# FC_Main.net
KiCad netlist of a schematic drawn in Altium Designer
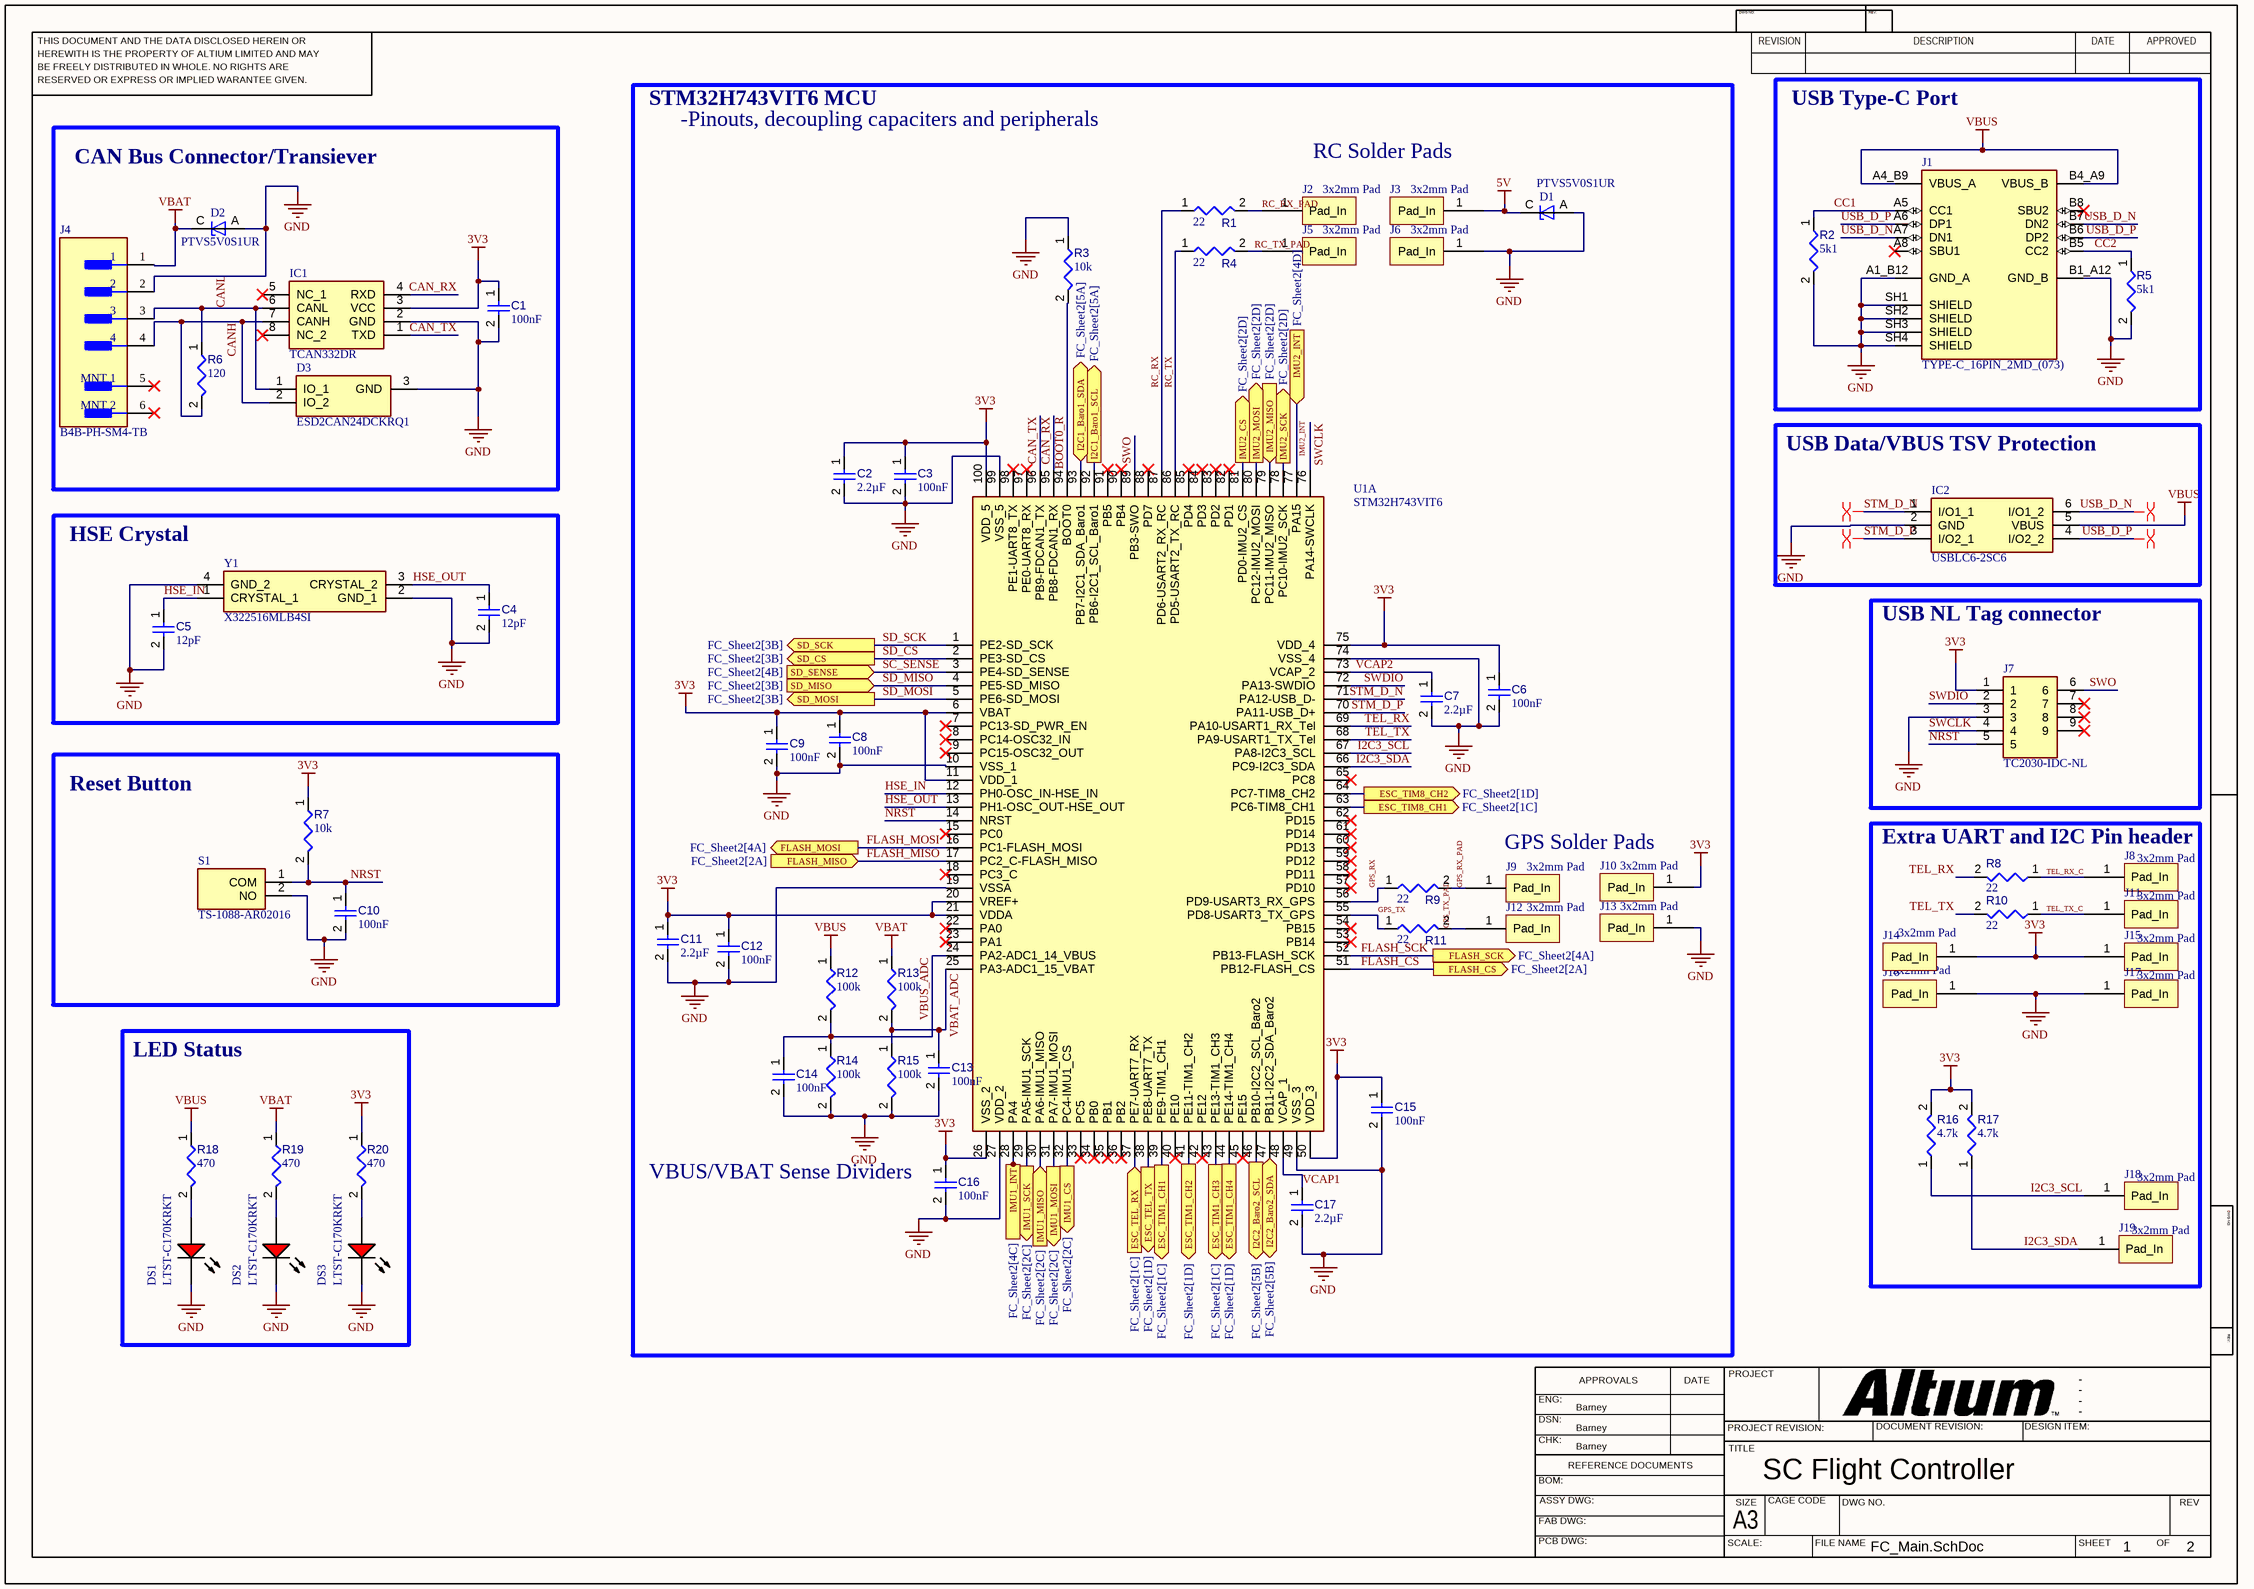
[diagram p0: FC_Main.SchDoc]

(export (version "E")
  (design (tool "Eeschema 10.0.6"))
  (components
    (comp (ref "C1")
      (value "100nF")
      (footprint "CAPC0402(1005)60_L")
      (description "Chip Capacitor, 100nF +/-20%, 10V, 0402, Thickness 0.6 mm")
      (fields (field (name "TOLERANCE") "20%") (field (name "Comment") "Capacitor 100nF +/-20% 10V 0402"))
      (libsource (lib "Barney's Workspace") (part "CAP-NP-2"))
    )
    (comp (ref "C2")
      (value "2.2µF")
      (footprint "CAPC0402(1005)60_L")
      (description "Chip Capacitor, 2,2µF +/-20%, 10V, 0402, Thickness 0.6 mm")
      (fields (field (name "TOLERANCE") "10%") (field (name "Comment") "Capacitor 2,2µF +/-20% 10V 0402"))
      (libsource (lib "Barney's Workspace") (part "CAP-NP-2"))
    )
    (comp (ref "C3")
      (value "100nF")
      (footprint "CAPC0402(1005)60_L")
      (description "Chip Capacitor, 100nF +/-20%, 10V, 0402, Thickness 0.6 mm")
      (fields (field (name "TOLERANCE") "20%") (field (name "Comment") "Capacitor 100nF +/-20% 10V 0402"))
      (libsource (lib "Barney's Workspace") (part "CAP-NP-2"))
    )
    (comp (ref "C4")
      (value "12pF")
      (footprint "CAPC0402(1005)33_L")
      (description "Chip Capacitor, 12pF +/-10%, 50V, 0402, Thickness 0.33 mm")
      (fields (field (name "TOLERANCE") "20%") (field (name "Comment") "Capacitor 12pF +/-10% 50V 0402"))
      (libsource (lib "Barney's Workspace") (part "CAP-NP-2"))
    )
    (comp (ref "C5")
      (value "12pF")
      (footprint "CAPC0402(1005)33_L")
      (description "Chip Capacitor, 12pF +/-10%, 50V, 0402, Thickness 0.33 mm")
      (fields (field (name "TOLERANCE") "20%") (field (name "Comment") "Capacitor 12pF +/-10% 50V 0402"))
      (libsource (lib "Barney's Workspace") (part "CAP-NP-2"))
    )
    (comp (ref "C6")
      (value "100nF")
      (footprint "CAPC0402(1005)60_L")
      (description "Chip Capacitor, 100nF +/-20%, 10V, 0402, Thickness 0.6 mm")
      (fields (field (name "TOLERANCE") "20%") (field (name "Comment") "Capacitor 100nF +/-20% 10V 0402"))
      (libsource (lib "Barney's Workspace") (part "CAP-NP-2"))
    )
    (comp (ref "C7")
      (value "2.2µF")
      (footprint "CAPC0402(1005)60_L")
      (description "Chip Capacitor, 2,2µF +/-20%, 10V, 0402, Thickness 0.6 mm")
      (fields (field (name "TOLERANCE") "10%") (field (name "Comment") "Capacitor 2,2µF +/-20% 10V 0402"))
      (libsource (lib "Barney's Workspace") (part "CAP-NP-2"))
    )
    (comp (ref "C8")
      (value "100nF")
      (footprint "CAPC0402(1005)60_L")
      (description "Chip Capacitor, 100nF +/-20%, 10V, 0402, Thickness 0.6 mm")
      (fields (field (name "TOLERANCE") "20%") (field (name "Comment") "Capacitor 100nF +/-20% 10V 0402"))
      (libsource (lib "Barney's Workspace") (part "CAP-NP-2"))
    )
    (comp (ref "C9")
      (value "100nF")
      (footprint "CAPC0402(1005)60_L")
      (description "Chip Capacitor, 100nF +/-20%, 10V, 0402, Thickness 0.6 mm")
      (fields (field (name "TOLERANCE") "20%") (field (name "Comment") "Capacitor 100nF +/-20% 10V 0402"))
      (libsource (lib "Barney's Workspace") (part "CAP-NP-2"))
    )
    (comp (ref "C10")
      (value "100nF")
      (footprint "CAPC0402(1005)60_L")
      (description "Chip Capacitor, 100nF +/-20%, 10V, 0402, Thickness 0.6 mm")
      (fields (field (name "TOLERANCE") "20%") (field (name "Comment") "Capacitor 100nF +/-20% 10V 0402"))
      (libsource (lib "Barney's Workspace") (part "CAP-NP-2"))
    )
    (comp (ref "C11")
      (value "2.2µF")
      (footprint "CAPC0402(1005)60_L")
      (description "Chip Capacitor, 2,2µF +/-20%, 10V, 0402, Thickness 0.6 mm")
      (fields (field (name "TOLERANCE") "10%") (field (name "Comment") "Capacitor 2,2µF +/-20% 10V 0402"))
      (libsource (lib "Barney's Workspace") (part "CAP-NP-2"))
    )
    (comp (ref "C12")
      (value "100nF")
      (footprint "CAPC0402(1005)60_L")
      (description "Chip Capacitor, 100nF +/-20%, 10V, 0402, Thickness 0.6 mm")
      (fields (field (name "TOLERANCE") "20%") (field (name "Comment") "Capacitor 100nF +/-20% 10V 0402"))
      (libsource (lib "Barney's Workspace") (part "CAP-NP-2"))
    )
    (comp (ref "C13")
      (value "100nF")
      (footprint "CAPC0402(1005)60_L")
      (description "Chip Capacitor, 100nF +/-20%, 10V, 0402, Thickness 0.6 mm")
      (fields (field (name "TOLERANCE") "20%") (field (name "Comment") "Capacitor 100nF +/-20% 10V 0402"))
      (libsource (lib "Barney's Workspace") (part "CAP-NP-2"))
    )
    (comp (ref "C14")
      (value "100nF")
      (footprint "CAPC0402(1005)60_L")
      (description "Chip Capacitor, 100nF +/-20%, 10V, 0402, Thickness 0.6 mm")
      (fields (field (name "TOLERANCE") "20%") (field (name "Comment") "Capacitor 100nF +/-20% 10V 0402"))
      (libsource (lib "Barney's Workspace") (part "CAP-NP-2"))
    )
    (comp (ref "C15")
      (value "100nF")
      (footprint "CAPC0402(1005)60_L")
      (description "Chip Capacitor, 100nF +/-20%, 10V, 0402, Thickness 0.6 mm")
      (fields (field (name "TOLERANCE") "20%") (field (name "Comment") "Capacitor 100nF +/-20% 10V 0402"))
      (libsource (lib "Barney's Workspace") (part "CAP-NP-2"))
    )
    (comp (ref "C16")
      (value "100nF")
      (footprint "CAPC0402(1005)60_L")
      (description "Chip Capacitor, 100nF +/-20%, 10V, 0402, Thickness 0.6 mm")
      (fields (field (name "TOLERANCE") "20%") (field (name "Comment") "Capacitor 100nF +/-20% 10V 0402"))
      (libsource (lib "Barney's Workspace") (part "CAP-NP-2"))
    )
    (comp (ref "C17")
      (value "2.2µF")
      (footprint "CAPC0402(1005)60_L")
      (description "Chip Capacitor, 2,2µF +/-20%, 10V, 0402, Thickness 0.6 mm")
      (fields (field (name "TOLERANCE") "10%") (field (name "Comment") "Capacitor 2,2µF +/-20% 10V 0402"))
      (libsource (lib "Barney's Workspace") (part "CAP-NP-2"))
    )
    (comp (ref "D1")
      (value "PTVS5V0S1UR")
      (footprint "TVS_PTVS5V0S1UR")
      (description "9.2V Clamp 43.5A Ipp Tvs Diode Surface Mount SOD-123W")
      (fields (field (name "MF") "Nexperia USA"))
      (libsource (lib "Barney's Workspace") (part "PTVS5V0S1UR"))
    )
    (comp (ref "D2")
      (value "PTVS5V0S1UR")
      (footprint "TVS_PTVS5V0S1UR")
      (description "9.2V Clamp 43.5A Ipp Tvs Diode Surface Mount SOD-123W")
      (fields (field (name "MF") "Nexperia USA"))
      (libsource (lib "Barney's Workspace") (part "PTVS5V0S1UR"))
    )
    (comp (ref "D3")
      (value "ESD2CAN24DCKRQ1")
      (footprint "SamacSys:SOT65P210X110-3N")
      (description "TVS Diode (Bi-directional)")
      (fields (field (name "MOUSER PART NUMBER") "595-ESD2CAN24DCKRQ1"))
      (libsource (lib "*") (part "ESD2CAN24DCKRQ1"))
    )
    (comp (ref "DS1")
      (value "LTST-C170KRKT")
      (footprint "LTST-C170KRKT_V")
      (description "LED Red, 75 mW, 54 mcd, -55 to 85 degC, 2-Pin SMD, RoHS, Tape and Reel")
      (fields (field (name "MANUFACTURER") "Lite-On"))
      (libsource (lib "Altium Content Vault") (part "LED-RED-AK-2"))
    )
    (comp (ref "DS2")
      (value "LTST-C170KRKT")
      (footprint "LTST-C170KRKT_V")
      (description "LED Red, 75 mW, 54 mcd, -55 to 85 degC, 2-Pin SMD, RoHS, Tape and Reel")
      (fields (field (name "MANUFACTURER") "Lite-On"))
      (libsource (lib "Altium Content Vault") (part "LED-RED-AK-2"))
    )
    (comp (ref "DS3")
      (value "LTST-C170KRKT")
      (footprint "LTST-C170KRKT_V")
      (description "LED Red, 75 mW, 54 mcd, -55 to 85 degC, 2-Pin SMD, RoHS, Tape and Reel")
      (fields (field (name "MANUFACTURER") "Lite-On"))
      (libsource (lib "Altium Content Vault") (part "LED-RED-AK-2"))
    )
    (comp (ref "IC1")
      (value "TCAN332DR")
      (footprint "SamacSys:SOIC127P600X175-8N")
      (description "Integrated Circuit")
      (fields (field (name "MOUSER PART NUMBER") "595-TCAN332DR"))
      (libsource (lib "*") (part "TCAN332DR"))
    )
    (comp (ref "IC2")
      (value "USBLC6-2SC6")
      (footprint "SamacSys:SOT95P280X145-6N")
      (description "Integrated Circuit")
      (fields (field (name "MOUSER PART NUMBER") "511-USBLC6-2SC6"))
      (libsource (lib "*") (part "USBLC6-2SC6"))
    )
    (comp (ref "J1")
      (value "TYPE-C_16PIN_2MD_(073)")
      (footprint "SHOUHAN_TYPE-C_16PIN_2MD_(073)")
      (description "DC-5V 5A Type C USB")
      (fields (field (name "MP") "TYPE-C 16PIN 2MD (073)") (field (name "MF") "Shouhan"))
      (libsource (lib "Barney's Workspace") (part "TYPE-C_16PIN_2MD_(073)"))
    )
    (comp (ref "J2")
      (value "3x2mm Pad")
      (footprint "3x2mm Pad-Footprint-1")
      (description "3mm x 2mm Pad to solder")
      (libsource (lib "Barney's Workspace") (part "3x2mm Pad-Symbol-1"))
    )
    (comp (ref "J3")
      (value "3x2mm Pad")
      (footprint "3x2mm Pad-Footprint-1")
      (description "3mm x 2mm Pad to solder")
      (libsource (lib "") (part "3x2mm Pad-Symbol-1_1"))
    )
    (comp (ref "J4")
      (value "B4B-PH-SM4-TB")
      (footprint "FP-B4B-PH-SM4-TB-MFG")
      (description "CONN HEADER SMD 4POS 2MM")
      (libsource (lib "Altium Content Vault") (part "f4320a1371cd6270e33bce1916c33c0"))
    )
    (comp (ref "J5")
      (value "3x2mm Pad")
      (footprint "3x2mm Pad-Footprint-1")
      (description "3mm x 2mm Pad to solder")
      (libsource (lib "Barney's Workspace") (part "3x2mm Pad-Symbol-1"))
    )
    (comp (ref "J6")
      (value "3x2mm Pad")
      (footprint "3x2mm Pad-Footprint-1")
      (description "3mm x 2mm Pad to solder")
      (libsource (lib "") (part "3x2mm Pad-Symbol-1_1"))
    )
    (comp (ref "J7")
      (value "TC2030-IDC-NL")
      (footprint "SamacSys:TC2030IDCNL")
      (description "Connector")
      (libsource (lib "*") (part "TC2030-IDC-NL"))
    )
    (comp (ref "J8")
      (value "3x2mm Pad")
      (footprint "3x2mm Pad-Footprint-1")
      (description "3mm x 2mm Pad to solder")
      (libsource (lib "Barney's Workspace") (part "3x2mm Pad-Symbol-1"))
    )
    (comp (ref "J9")
      (value "3x2mm Pad")
      (footprint "3x2mm Pad-Footprint-1")
      (description "3mm x 2mm Pad to solder")
      (libsource (lib "Barney's Workspace") (part "3x2mm Pad-Symbol-1"))
    )
    (comp (ref "J10")
      (value "3x2mm Pad")
      (footprint "3x2mm Pad-Footprint-1")
      (description "3mm x 2mm Pad to solder")
      (libsource (lib "") (part "3x2mm Pad-Symbol-1_1"))
    )
    (comp (ref "J11")
      (value "3x2mm Pad")
      (footprint "3x2mm Pad-Footprint-1")
      (description "3mm x 2mm Pad to solder")
      (libsource (lib "Barney's Workspace") (part "3x2mm Pad-Symbol-1"))
    )
    (comp (ref "J12")
      (value "3x2mm Pad")
      (footprint "3x2mm Pad-Footprint-1")
      (description "3mm x 2mm Pad to solder")
      (libsource (lib "Barney's Workspace") (part "3x2mm Pad-Symbol-1"))
    )
    (comp (ref "J13")
      (value "3x2mm Pad")
      (footprint "3x2mm Pad-Footprint-1")
      (description "3mm x 2mm Pad to solder")
      (libsource (lib "") (part "3x2mm Pad-Symbol-1_1"))
    )
    (comp (ref "J14")
      (value "3x2mm Pad")
      (footprint "3x2mm Pad-Footprint-1")
      (description "3mm x 2mm Pad to solder")
      (libsource (lib "") (part "3x2mm Pad-Symbol-1_1"))
    )
    (comp (ref "J15")
      (value "3x2mm Pad")
      (footprint "3x2mm Pad-Footprint-1")
      (description "3mm x 2mm Pad to solder")
      (libsource (lib "Barney's Workspace") (part "3x2mm Pad-Symbol-1"))
    )
    (comp (ref "J16")
      (value "3x2mm Pad")
      (footprint "3x2mm Pad-Footprint-1")
      (description "3mm x 2mm Pad to solder")
      (libsource (lib "") (part "3x2mm Pad-Symbol-1_1"))
    )
    (comp (ref "J17")
      (value "3x2mm Pad")
      (footprint "3x2mm Pad-Footprint-1")
      (description "3mm x 2mm Pad to solder")
      (libsource (lib "Barney's Workspace") (part "3x2mm Pad-Symbol-1"))
    )
    (comp (ref "J18")
      (value "3x2mm Pad")
      (footprint "3x2mm Pad-Footprint-1")
      (description "3mm x 2mm Pad to solder")
      (libsource (lib "Barney's Workspace") (part "3x2mm Pad-Symbol-1"))
    )
    (comp (ref "J19")
      (value "3x2mm Pad")
      (footprint "3x2mm Pad-Footprint-1")
      (description "3mm x 2mm Pad to solder")
      (libsource (lib "Barney's Workspace") (part "3x2mm Pad-Symbol-1"))
    )
    (comp (ref "R1")
      (value "22")
      (footprint "RESC0402(1005)_L")
      (description "Chip Resistor, 22Ohms, +/-1 %, 63 mW, -55 to 155 degC, 0402")
      (fields (field (name "TOLERANCE") "1%") (field (name "POWER") "63mW"))
      (libsource (lib "Barney's Workspace") (part "RES-2"))
    )
    (comp (ref "R2")
      (value "5k1")
      (footprint "RESC0402(1005)_L")
      (description "Chip Resistor, 5.1 kOhms, +/-1 %, 63 mW, -55 to 155 degC, 0402")
      (fields (field (name "TOLERANCE") "1%") (field (name "POWER") "63mW"))
      (libsource (lib "Barney's Workspace") (part "RES-2"))
    )
    (comp (ref "R3")
      (value "10k")
      (footprint "RESC0402(1005)_L")
      (description "Chip Resistor, 10 kOhms, +/-1 %, 63 mW, -55 to 125 degC, 0402")
      (fields (field (name "POWER") "63mW") (field (name "TOLERANCE") "1%"))
      (libsource (lib "Barney's Workspace") (part "RES-2"))
    )
    (comp (ref "R4")
      (value "22")
      (footprint "RESC0402(1005)_L")
      (description "Chip Resistor, 22Ohms, +/-1 %, 63 mW, -55 to 155 degC, 0402")
      (fields (field (name "TOLERANCE") "1%") (field (name "POWER") "63mW"))
      (libsource (lib "Barney's Workspace") (part "RES-2"))
    )
    (comp (ref "R5")
      (value "5k1")
      (footprint "RESC0402(1005)_L")
      (description "Chip Resistor, 5.1 kOhms, +/-1 %, 63 mW, -55 to 155 degC, 0402")
      (fields (field (name "TOLERANCE") "1%") (field (name "POWER") "63mW"))
      (libsource (lib "Barney's Workspace") (part "RES-2"))
    )
    (comp (ref "R6")
      (value "120")
      (footprint "RESC0402(1005)_L")
      (description "Chip Resistor, 120 Ohms, +/-1 %, 63 mW, -55 to 155 degC, 0402")
      (fields (field (name "TOLERANCE") "1%") (field (name "POWER") "63mW"))
      (libsource (lib "Barney's Workspace") (part "RES-2"))
    )
    (comp (ref "R7")
      (value "10k")
      (footprint "RESC0402(1005)_L")
      (description "Chip Resistor, 10 kOhms, +/-1 %, 63 mW, -55 to 125 degC, 0402")
      (fields (field (name "POWER") "63mW") (field (name "TOLERANCE") "1%"))
      (libsource (lib "Barney's Workspace") (part "RES-2"))
    )
    (comp (ref "R8")
      (value "22")
      (footprint "RESC0402(1005)_L")
      (description "Chip Resistor, 22Ohms, +/-1 %, 63 mW, -55 to 155 degC, 0402")
      (fields (field (name "TOLERANCE") "1%") (field (name "POWER") "63mW"))
      (libsource (lib "Barney's Workspace") (part "RES-2"))
    )
    (comp (ref "R9")
      (value "22")
      (footprint "RESC0402(1005)_L")
      (description "Chip Resistor, 22Ohms, +/-1 %, 63 mW, -55 to 155 degC, 0402")
      (fields (field (name "TOLERANCE") "1%") (field (name "POWER") "63mW"))
      (libsource (lib "Barney's Workspace") (part "RES-2"))
    )
    (comp (ref "R10")
      (value "22")
      (footprint "RESC0402(1005)_L")
      (description "Chip Resistor, 22Ohms, +/-1 %, 63 mW, -55 to 155 degC, 0402")
      (fields (field (name "TOLERANCE") "1%") (field (name "POWER") "63mW"))
      (libsource (lib "Barney's Workspace") (part "RES-2"))
    )
    (comp (ref "R11")
      (value "22")
      (footprint "RESC0402(1005)_L")
      (description "Chip Resistor, 22Ohms, +/-1 %, 63 mW, -55 to 155 degC, 0402")
      (fields (field (name "TOLERANCE") "1%") (field (name "POWER") "63mW"))
      (libsource (lib "Barney's Workspace") (part "RES-2"))
    )
    (comp (ref "R12")
      (value "100k")
      (footprint "RESC0402(1005)_L")
      (description "Chip Resistor, 100 kOhms, +/-1 %, 63 mW, -55 to 155 degC, 0402")
      (fields (field (name "TOLERANCE") "1%") (field (name "POWER") "63mW"))
      (libsource (lib "Barney's Workspace") (part "RES-2"))
    )
    (comp (ref "R13")
      (value "100k")
      (footprint "RESC0402(1005)_L")
      (description "Chip Resistor, 100 kOhms, +/-1 %, 63 mW, -55 to 155 degC, 0402")
      (fields (field (name "TOLERANCE") "1%") (field (name "POWER") "63mW"))
      (libsource (lib "Barney's Workspace") (part "RES-2"))
    )
    (comp (ref "R14")
      (value "100k")
      (footprint "RESC0402(1005)_L")
      (description "Chip Resistor, 100 kOhms, +/-1 %, 63 mW, -55 to 155 degC, 0402")
      (fields (field (name "TOLERANCE") "1%") (field (name "POWER") "63mW"))
      (libsource (lib "Barney's Workspace") (part "RES-2"))
    )
    (comp (ref "R15")
      (value "100k")
      (footprint "RESC0402(1005)_L")
      (description "Chip Resistor, 100 kOhms, +/-1 %, 63 mW, -55 to 155 degC, 0402")
      (fields (field (name "TOLERANCE") "1%") (field (name "POWER") "63mW"))
      (libsource (lib "Barney's Workspace") (part "RES-2"))
    )
    (comp (ref "R16")
      (value "4.7k")
      (footprint "RESC0402(1005)_L")
      (description "4K7 0.063W 1% 0402 (1005 Metric)  SMD")
      (fields (field (name "TOLERANCE") "1%") (field (name "POWER") "63mW"))
      (libsource (lib "Barney's Workspace") (part "4D7KR2F"))
    )
    (comp (ref "R17")
      (value "4.7k")
      (footprint "RESC0402(1005)_L")
      (description "4K7 0.063W 1% 0402 (1005 Metric)  SMD")
      (fields (field (name "TOLERANCE") "1%") (field (name "POWER") "63mW"))
      (libsource (lib "Barney's Workspace") (part "4D7KR2F"))
    )
    (comp (ref "R18")
      (value "470")
      (footprint "RESC0805(2012)_L")
      (description "Chip Resistor, 470 Ohms, +/-5%, 125 mW, -55 to 155 degC, 0805")
      (fields (field (name "TOLERANCE") "5%") (field (name "POWER") "125mW"))
      (libsource (lib "Barney's Workspace") (part "RES-2"))
    )
    (comp (ref "R19")
      (value "470")
      (footprint "RESC0805(2012)_L")
      (description "Chip Resistor, 470 Ohms, +/-5%, 125 mW, -55 to 155 degC, 0805")
      (fields (field (name "TOLERANCE") "5%") (field (name "POWER") "125mW"))
      (libsource (lib "Barney's Workspace") (part "RES-2"))
    )
    (comp (ref "R20")
      (value "470")
      (footprint "RESC0805(2012)_L")
      (description "Chip Resistor, 470 Ohms, +/-5%, 125 mW, -55 to 155 degC, 0805")
      (fields (field (name "TOLERANCE") "5%") (field (name "POWER") "125mW"))
      (libsource (lib "Barney's Workspace") (part "RES-2"))
    )
    (comp (ref "S1")
      (value "TS-1088-AR02016")
      (footprint "SamacSys:TS1088AR02016")
      (description "Switch")
      (libsource (lib "*") (part "TS-1088-AR02016"))
    )
    (comp (ref "U1")
      (value "STM32H743VIT6")
      (footprint "QFP50P1600X1600X160-100N")
      (libsource (lib "Barney's Workspace") (part "STM32H743VIT6"))
    )
    (comp (ref "Y1")
      (value "X322516MLB4SI")
      (footprint "SamacSys:X322516MLB4SI")
      (description "Crystal or Oscillator")
      (libsource (lib "*") (part "X322516MLB4SI"))
    )
  )
  (nets
    (net (code "1") (name "/BOOT0_R") (class "Default")
      (node (ref "R3") (pin "2") (pinfunction "2_2") (pintype "passive"))
      (node (ref "U1") (pin "94") (pinfunction "BOOT0_94") (pintype "passive"))
    )
    (net (code "2") (name "/CANH") (class "Default")
      (node (ref "D3") (pin "2") (pinfunction "IO_2_2") (pintype "passive"))
      (node (ref "IC1") (pin "7") (pinfunction "CANH_7") (pintype "passive"))
      (node (ref "J4") (pin "4") (pinfunction "4_4") (pintype "passive"))
      (node (ref "R6") (pin "2") (pinfunction "2_2") (pintype "passive"))
    )
    (net (code "3") (name "/CANL") (class "Default")
      (node (ref "D3") (pin "1") (pinfunction "IO_1_1") (pintype "passive"))
      (node (ref "IC1") (pin "6") (pinfunction "CANL_6") (pintype "passive"))
      (node (ref "J4") (pin "3") (pinfunction "3_3") (pintype "passive"))
      (node (ref "R6") (pin "1") (pinfunction "1_1") (pintype "passive"))
    )
    (net (code "4") (name "/CAN_RX") (class "Default")
      (node (ref "IC1") (pin "4") (pinfunction "RXD_4") (pintype "passive"))
      (node (ref "U1") (pin "95") (pinfunction "PB8-FDCAN1_RX_95") (pintype "passive"))
    )
    (net (code "5") (name "/CAN_TX") (class "Default")
      (node (ref "IC1") (pin "1") (pinfunction "TXD_1") (pintype "passive"))
      (node (ref "U1") (pin "96") (pinfunction "PB9-FDCAN1_TX_96") (pintype "passive"))
    )
    (net (code "6") (name "/CC1") (class "Default")
      (node (ref "J1") (pin "A5") (pinfunction "CC1_A5") (pintype "bidirectional"))
      (node (ref "R2") (pin "1") (pinfunction "1_1") (pintype "passive"))
    )
    (net (code "7") (name "/CC2") (class "Default")
      (node (ref "J1") (pin "B5") (pinfunction "CC2_B5") (pintype "bidirectional"))
      (node (ref "R5") (pin "1") (pinfunction "1_1") (pintype "passive"))
    )
    (net (code "8") (name "/ESC_TEL_RX") (class "Default")
      (node (ref "U1") (pin "37") (pinfunction "PE7-UART7_RX_37") (pintype "passive"))
    )
    (net (code "9") (name "/ESC_TEL_TX") (class "Default")
      (node (ref "U1") (pin "38") (pinfunction "PE8-UART7_TX_38") (pintype "passive"))
    )
    (net (code "10") (name "/ESC_TIM1_CH1") (class "Default")
      (node (ref "U1") (pin "39") (pinfunction "PE9-TIM1_CH1_39") (pintype "passive"))
    )
    (net (code "11") (name "/ESC_TIM1_CH2") (class "Default")
      (node (ref "U1") (pin "41") (pinfunction "PE11-TIM1_CH2_41") (pintype "passive"))
    )
    (net (code "12") (name "/ESC_TIM1_CH3") (class "Default")
      (node (ref "U1") (pin "43") (pinfunction "PE13-TIM1_CH3_43") (pintype "passive"))
    )
    (net (code "13") (name "/ESC_TIM1_CH4") (class "Default")
      (node (ref "U1") (pin "44") (pinfunction "PE14-TIM1_CH4_44") (pintype "passive"))
    )
    (net (code "14") (name "/ESC_TIM8_CH1") (class "Default")
      (node (ref "U1") (pin "63") (pinfunction "PC6-TIM8_CH1_63") (pintype "passive"))
    )
    (net (code "15") (name "/ESC_TIM8_CH2") (class "Default")
      (node (ref "U1") (pin "64") (pinfunction "PC7-TIM8_CH2_64") (pintype "passive"))
    )
    (net (code "16") (name "/FLASH_CS") (class "Default")
      (node (ref "U1") (pin "51") (pinfunction "PB12-FLASH_CS_51") (pintype "passive"))
    )
    (net (code "17") (name "/FLASH_MISO") (class "Default")
      (node (ref "U1") (pin "17") (pinfunction "PC2_C-FLASH_MISO_17") (pintype "passive"))
    )
    (net (code "18") (name "/FLASH_MOSI") (class "Default")
      (node (ref "U1") (pin "16") (pinfunction "PC1-FLASH_MOSI_16") (pintype "passive"))
    )
    (net (code "19") (name "/FLASH_SCK") (class "Default")
      (node (ref "U1") (pin "52") (pinfunction "PB13-FLASH_SCK_52") (pintype "passive"))
    )
    (net (code "20") (name "/GPS_RX") (class "Default")
      (node (ref "R9") (pin "1") (pinfunction "1_1") (pintype "passive"))
      (node (ref "U1") (pin "56") (pinfunction "PD9-USART3_RX_GPS_56") (pintype "passive"))
    )
    (net (code "21") (name "/GPS_RX_PAD") (class "Default")
      (node (ref "J9") (pin "1") (pinfunction "Pad_In_1") (pintype "passive"))
      (node (ref "R9") (pin "2") (pinfunction "2_2") (pintype "passive"))
    )
    (net (code "22") (name "/GPS_TX") (class "Default")
      (node (ref "R11") (pin "1") (pinfunction "1_1") (pintype "passive"))
      (node (ref "U1") (pin "55") (pinfunction "PD8-USART3_TX_GPS_55") (pintype "passive"))
    )
    (net (code "23") (name "/GPS_TX_PAD") (class "Default")
      (node (ref "J12") (pin "1") (pinfunction "Pad_In_1") (pintype "passive"))
      (node (ref "R11") (pin "2") (pinfunction "2_2") (pintype "passive"))
    )
    (net (code "24") (name "/HSE_IN") (class "Default")
      (node (ref "C5") (pin "1") (pinfunction "1_1") (pintype "passive"))
      (node (ref "U1") (pin "12") (pinfunction "PH0-OSC_IN-HSE_IN_12") (pintype "passive"))
      (node (ref "Y1") (pin "1") (pinfunction "CRYSTAL_1_1") (pintype "passive"))
    )
    (net (code "25") (name "/HSE_OUT") (class "Default")
      (node (ref "C4") (pin "1") (pinfunction "1_1") (pintype "passive"))
      (node (ref "U1") (pin "13") (pinfunction "PH1-OSC_OUT-HSE_OUT_13") (pintype "passive"))
      (node (ref "Y1") (pin "3") (pinfunction "CRYSTAL_2_3") (pintype "passive"))
    )
    (net (code "26") (name "/I2C1_Baro1_SCL") (class "Default")
      (node (ref "U1") (pin "92") (pinfunction "PB6-I2C1_SCL_Baro1_92") (pintype "passive"))
    )
    (net (code "27") (name "/I2C1_Baro1_SDA") (class "Default")
      (node (ref "U1") (pin "93") (pinfunction "PB7-I2C1_SDA_Baro1_93") (pintype "passive"))
    )
    (net (code "28") (name "/I2C2_Baro2_SCL") (class "Default")
      (node (ref "U1") (pin "46") (pinfunction "PB10-I2C2_SCL_Baro2_46") (pintype "passive"))
    )
    (net (code "29") (name "/I2C2_Baro2_SDA") (class "Default")
      (node (ref "U1") (pin "47") (pinfunction "PB11-I2C2_SDA_Baro2_47") (pintype "passive"))
    )
    (net (code "30") (name "/I2C3_SCL") (class "Default")
      (node (ref "J18") (pin "1") (pinfunction "Pad_In_1") (pintype "passive"))
      (node (ref "R16") (pin "1") (pinfunction "1_1") (pintype "passive"))
      (node (ref "U1") (pin "67") (pinfunction "PA8-I2C3_SCL_67") (pintype "passive"))
    )
    (net (code "31") (name "/I2C3_SDA") (class "Default")
      (node (ref "J19") (pin "1") (pinfunction "Pad_In_1") (pintype "passive"))
      (node (ref "R17") (pin "1") (pinfunction "1_1") (pintype "passive"))
      (node (ref "U1") (pin "66") (pinfunction "PC9-I2C3_SDA_66") (pintype "passive"))
    )
    (net (code "32") (name "/IMU1_CS") (class "Default")
      (node (ref "U1") (pin "32") (pinfunction "PC4-IMU1_CS_32") (pintype "passive"))
    )
    (net (code "33") (name "/IMU1_INT") (class "Default")
      (node (ref "U1") (pin "28") (pinfunction "PA4_28") (pintype "passive"))
    )
    (net (code "34") (name "/IMU1_MISO") (class "Default")
      (node (ref "U1") (pin "30") (pinfunction "PA6-IMU1_MISO_30") (pintype "passive"))
    )
    (net (code "35") (name "/IMU1_MOSI") (class "Default")
      (node (ref "U1") (pin "31") (pinfunction "PA7-IMU1_MOSI_31") (pintype "passive"))
    )
    (net (code "36") (name "/IMU1_SCK") (class "Default")
      (node (ref "U1") (pin "29") (pinfunction "PA5-IMU1_SCK_29") (pintype "passive"))
    )
    (net (code "37") (name "/IMU2_CS") (class "Default")
      (node (ref "U1") (pin "81") (pinfunction "PD0-IMU2_CS_81") (pintype "passive"))
    )
    (net (code "38") (name "/IMU2_INT") (class "Default")
      (node (ref "U1") (pin "77") (pinfunction "PA15_77") (pintype "passive"))
    )
    (net (code "39") (name "/IMU2_MISO") (class "Default")
      (node (ref "U1") (pin "79") (pinfunction "PC11-IMU2_MISO_79") (pintype "passive"))
    )
    (net (code "40") (name "/IMU2_MOSI") (class "Default")
      (node (ref "U1") (pin "80") (pinfunction "PC12-IMU2_MOSI_80") (pintype "passive"))
    )
    (net (code "41") (name "/IMU2_SCK") (class "Default")
      (node (ref "U1") (pin "78") (pinfunction "PC10-IMU2_SCK_78") (pintype "passive"))
    )
    (net (code "42") (name "/NRST") (class "Default")
      (node (ref "C10") (pin "1") (pinfunction "1_1") (pintype "passive"))
      (node (ref "J7") (pin "5") (pinfunction "5_5") (pintype "passive"))
      (node (ref "R7") (pin "2") (pinfunction "2_2") (pintype "passive"))
      (node (ref "S1") (pin "1") (pinfunction "COM_1") (pintype "passive"))
      (node (ref "U1") (pin "14") (pinfunction "NRST_14") (pintype "passive"))
    )
    (net (code "43") (name "/RC_RX") (class "Default")
      (node (ref "R1") (pin "1") (pinfunction "1_1") (pintype "passive"))
      (node (ref "U1") (pin "87") (pinfunction "PD6-USART2_RX_RC_87") (pintype "passive"))
    )
    (net (code "44") (name "/RC_RX_PAD") (class "Default")
      (node (ref "J2") (pin "1") (pinfunction "Pad_In_1") (pintype "passive"))
      (node (ref "R1") (pin "2") (pinfunction "2_2") (pintype "passive"))
    )
    (net (code "45") (name "/RC_TX") (class "Default")
      (node (ref "R4") (pin "1") (pinfunction "1_1") (pintype "passive"))
      (node (ref "U1") (pin "86") (pinfunction "PD5-USART2_TX_RC_86") (pintype "passive"))
    )
    (net (code "46") (name "/RC_TX_PAD") (class "Default")
      (node (ref "J5") (pin "1") (pinfunction "Pad_In_1") (pintype "passive"))
      (node (ref "R4") (pin "2") (pinfunction "2_2") (pintype "passive"))
    )
    (net (code "47") (name "/SC_SENSE") (class "Default")
      (node (ref "U1") (pin "3") (pinfunction "PE4-SD_SENSE_3") (pintype "passive"))
    )
    (net (code "48") (name "/SD_CS") (class "Default")
      (node (ref "U1") (pin "2") (pinfunction "PE3-SD_CS_2") (pintype "passive"))
    )
    (net (code "49") (name "/SD_MISO") (class "Default")
      (node (ref "U1") (pin "4") (pinfunction "PE5-SD_MISO_4") (pintype "passive"))
    )
    (net (code "50") (name "/SD_MOSI") (class "Default")
      (node (ref "U1") (pin "5") (pinfunction "PE6-SD_MOSI_5") (pintype "passive"))
    )
    (net (code "51") (name "/SD_SCK") (class "Default")
      (node (ref "U1") (pin "1") (pinfunction "PE2-SD_SCK_1") (pintype "passive"))
    )
    (net (code "52") (name "/STM_D_N") (class "Default")
      (node (ref "IC2") (pin "1") (pinfunction "I/O1_1_1") (pintype "passive"))
      (node (ref "U1") (pin "71") (pinfunction "PA12-USB_D-_71") (pintype "passive"))
    )
    (net (code "53") (name "/STM_D_P") (class "Default")
      (node (ref "IC2") (pin "3") (pinfunction "I/O2_1_3") (pintype "passive"))
      (node (ref "U1") (pin "70") (pinfunction "PA11-USB_D+_70") (pintype "passive"))
    )
    (net (code "54") (name "/SWCLK") (class "Default")
      (node (ref "J7") (pin "4") (pinfunction "4_4") (pintype "passive"))
      (node (ref "U1") (pin "76") (pinfunction "PA14-SWCLK_76") (pintype "passive"))
    )
    (net (code "55") (name "/SWDIO") (class "Default")
      (node (ref "J7") (pin "2") (pinfunction "2_2") (pintype "passive"))
      (node (ref "U1") (pin "72") (pinfunction "PA13-SWDIO_72") (pintype "passive"))
    )
    (net (code "56") (name "/SWO") (class "Default")
      (node (ref "J7") (pin "6") (pinfunction "6_6") (pintype "passive"))
      (node (ref "U1") (pin "89") (pinfunction "PB3-SWO_89") (pintype "passive"))
    )
    (net (code "57") (name "/TEL_RX") (class "Default")
      (node (ref "R8") (pin "2") (pinfunction "2_2") (pintype "passive"))
      (node (ref "U1") (pin "69") (pinfunction "PA10-USART1_RX_Tel_69") (pintype "passive"))
    )
    (net (code "58") (name "/TEL_RX_C") (class "Default")
      (node (ref "J8") (pin "1") (pinfunction "Pad_In_1") (pintype "passive"))
      (node (ref "R8") (pin "1") (pinfunction "1_1") (pintype "passive"))
    )
    (net (code "59") (name "/TEL_TX") (class "Default")
      (node (ref "R10") (pin "2") (pinfunction "2_2") (pintype "passive"))
      (node (ref "U1") (pin "68") (pinfunction "PA9-USART1_TX_Tel_68") (pintype "passive"))
    )
    (net (code "60") (name "/TEL_TX_C") (class "Default")
      (node (ref "J11") (pin "1") (pinfunction "Pad_In_1") (pintype "passive"))
      (node (ref "R10") (pin "1") (pinfunction "1_1") (pintype "passive"))
    )
    (net (code "61") (name "/USB_D_N") (class "Default")
      (node (ref "IC2") (pin "6") (pinfunction "I/O1_2_6") (pintype "passive"))
      (node (ref "J1") (pin "A7") (pinfunction "DN1_A7") (pintype "bidirectional"))
      (node (ref "J1") (pin "B7") (pinfunction "DN2_B7") (pintype "bidirectional"))
    )
    (net (code "62") (name "/USB_D_P") (class "Default")
      (node (ref "IC2") (pin "4") (pinfunction "I/O2_2_4") (pintype "passive"))
      (node (ref "J1") (pin "A6") (pinfunction "DP1_A6") (pintype "bidirectional"))
      (node (ref "J1") (pin "B6") (pinfunction "DP2_B6") (pintype "bidirectional"))
    )
    (net (code "63") (name "/VBAT_ADC") (class "Default")
      (node (ref "C13") (pin "1") (pinfunction "1_1") (pintype "passive"))
      (node (ref "R13") (pin "2") (pinfunction "2_2") (pintype "passive"))
      (node (ref "R15") (pin "1") (pinfunction "1_1") (pintype "passive"))
      (node (ref "U1") (pin "25") (pinfunction "PA3-ADC1_15_VBAT_25") (pintype "passive"))
    )
    (net (code "64") (name "/VBUS_ADC") (class "Default")
      (node (ref "C14") (pin "1") (pinfunction "1_1") (pintype "passive"))
      (node (ref "R12") (pin "2") (pinfunction "2_2") (pintype "passive"))
      (node (ref "R14") (pin "1") (pinfunction "1_1") (pintype "passive"))
      (node (ref "U1") (pin "24") (pinfunction "PA2-ADC1_14_VBUS_24") (pintype "passive"))
    )
    (net (code "65") (name "/VCAP1") (class "Default")
      (node (ref "C17") (pin "1") (pinfunction "1_1") (pintype "passive"))
      (node (ref "U1") (pin "48") (pinfunction "VCAP_1_48") (pintype "passive"))
    )
    (net (code "66") (name "/VCAP2") (class "Default")
      (node (ref "C7") (pin "1") (pinfunction "1_1") (pintype "passive"))
      (node (ref "U1") (pin "73") (pinfunction "VCAP_2_73") (pintype "passive"))
    )
    (net (code "67") (name "3V3") (class "Default")
      (node (ref "C1") (pin "1") (pinfunction "1_1") (pintype "passive"))
      (node (ref "C11") (pin "1") (pinfunction "1_1") (pintype "passive"))
      (node (ref "C12") (pin "1") (pinfunction "1_1") (pintype "passive"))
      (node (ref "C15") (pin "1") (pinfunction "1_1") (pintype "passive"))
      (node (ref "C16") (pin "1") (pinfunction "1_1") (pintype "passive"))
      (node (ref "C2") (pin "1") (pinfunction "1_1") (pintype "passive"))
      (node (ref "C3") (pin "1") (pinfunction "1_1") (pintype "passive"))
      (node (ref "C6") (pin "1") (pinfunction "1_1") (pintype "passive"))
      (node (ref "C8") (pin "1") (pinfunction "1_1") (pintype "passive"))
      (node (ref "C9") (pin "1") (pinfunction "1_1") (pintype "passive"))
      (node (ref "IC1") (pin "3") (pinfunction "VCC_3") (pintype "passive"))
      (node (ref "J10") (pin "1") (pinfunction "Pad_In_1") (pintype "passive"))
      (node (ref "J14") (pin "1") (pinfunction "Pad_In_1") (pintype "passive"))
      (node (ref "J15") (pin "1") (pinfunction "Pad_In_1") (pintype "passive"))
      (node (ref "J7") (pin "1") (pinfunction "1_1") (pintype "passive"))
      (node (ref "R16") (pin "2") (pinfunction "2_2") (pintype "passive"))
      (node (ref "R17") (pin "2") (pinfunction "2_2") (pintype "passive"))
      (node (ref "R20") (pin "1") (pinfunction "1_1") (pintype "passive"))
      (node (ref "R7") (pin "1") (pinfunction "1_1") (pintype "passive"))
      (node (ref "U1") (pin "100") (pinfunction "VDD_5_100") (pintype "passive"))
      (node (ref "U1") (pin "11") (pinfunction "VDD_1_11") (pintype "passive"))
      (node (ref "U1") (pin "20") (pinfunction "VREF+_20") (pintype "passive"))
      (node (ref "U1") (pin "21") (pinfunction "VDDA_21") (pintype "passive"))
      (node (ref "U1") (pin "26") (pinfunction "VSS_2_26") (pintype "passive"))
      (node (ref "U1") (pin "50") (pinfunction "VDD_3_50") (pintype "passive"))
      (node (ref "U1") (pin "6") (pinfunction "VBAT_6") (pintype "passive"))
      (node (ref "U1") (pin "75") (pinfunction "VDD_4_75") (pintype "passive"))
    )
    (net (code "68") (name "5V") (class "Default")
      (node (ref "D1") (pin "C") (pinfunction "C_C") (pintype "passive"))
      (node (ref "J3") (pin "1") (pinfunction "Pad_In_1") (pintype "passive"))
    )
    (net (code "69") (name "GND") (class "Default")
      (node (ref "C1") (pin "2") (pinfunction "2_2") (pintype "passive"))
      (node (ref "C10") (pin "2") (pinfunction "2_2") (pintype "passive"))
      (node (ref "C11") (pin "2") (pinfunction "2_2") (pintype "passive"))
      (node (ref "C12") (pin "2") (pinfunction "2_2") (pintype "passive"))
      (node (ref "C13") (pin "2") (pinfunction "2_2") (pintype "passive"))
      (node (ref "C14") (pin "2") (pinfunction "2_2") (pintype "passive"))
      (node (ref "C15") (pin "2") (pinfunction "2_2") (pintype "passive"))
      (node (ref "C16") (pin "2") (pinfunction "2_2") (pintype "passive"))
      (node (ref "C17") (pin "2") (pinfunction "2_2") (pintype "passive"))
      (node (ref "C2") (pin "2") (pinfunction "2_2") (pintype "passive"))
      (node (ref "C3") (pin "2") (pinfunction "2_2") (pintype "passive"))
      (node (ref "C4") (pin "2") (pinfunction "2_2") (pintype "passive"))
      (node (ref "C5") (pin "2") (pinfunction "2_2") (pintype "passive"))
      (node (ref "C6") (pin "2") (pinfunction "2_2") (pintype "passive"))
      (node (ref "C7") (pin "2") (pinfunction "2_2") (pintype "passive"))
      (node (ref "C8") (pin "2") (pinfunction "2_2") (pintype "passive"))
      (node (ref "C9") (pin "2") (pinfunction "2_2") (pintype "passive"))
      (node (ref "D1") (pin "A") (pinfunction "A_A") (pintype "passive"))
      (node (ref "D2") (pin "A") (pinfunction "A_A") (pintype "passive"))
      (node (ref "D3") (pin "3") (pinfunction "GND_3") (pintype "passive"))
      (node (ref "DS1") (pin "2") (pinfunction "K_2") (pintype "passive"))
      (node (ref "DS2") (pin "2") (pinfunction "K_2") (pintype "passive"))
      (node (ref "DS3") (pin "2") (pinfunction "K_2") (pintype "passive"))
      (node (ref "IC1") (pin "2") (pinfunction "GND_2") (pintype "passive"))
      (node (ref "IC2") (pin "2") (pinfunction "GND_2") (pintype "passive"))
      (node (ref "J1") (pin "A1_B12") (pinfunction "GND_A_A1_B12") (pintype "power_in"))
      (node (ref "J1") (pin "B1_A12") (pinfunction "GND_B_B1_A12") (pintype "power_in"))
      (node (ref "J1") (pin "SH1") (pinfunction "SHIELD_SH1") (pintype "passive"))
      (node (ref "J1") (pin "SH2") (pinfunction "SHIELD_SH2") (pintype "passive"))
      (node (ref "J1") (pin "SH3") (pinfunction "SHIELD_SH3") (pintype "passive"))
      (node (ref "J1") (pin "SH4") (pinfunction "SHIELD_SH4") (pintype "passive"))
      (node (ref "J13") (pin "1") (pinfunction "Pad_In_1") (pintype "passive"))
      (node (ref "J16") (pin "1") (pinfunction "Pad_In_1") (pintype "passive"))
      (node (ref "J17") (pin "1") (pinfunction "Pad_In_1") (pintype "passive"))
      (node (ref "J4") (pin "2") (pinfunction "2_2") (pintype "passive"))
      (node (ref "J6") (pin "1") (pinfunction "Pad_In_1") (pintype "passive"))
      (node (ref "J7") (pin "3") (pinfunction "3_3") (pintype "passive"))
      (node (ref "R14") (pin "2") (pinfunction "2_2") (pintype "passive"))
      (node (ref "R15") (pin "2") (pinfunction "2_2") (pintype "passive"))
      (node (ref "R2") (pin "2") (pinfunction "2_2") (pintype "passive"))
      (node (ref "R3") (pin "1") (pinfunction "1_1") (pintype "passive"))
      (node (ref "R5") (pin "2") (pinfunction "2_2") (pintype "passive"))
      (node (ref "S1") (pin "2") (pinfunction "NO_2") (pintype "passive"))
      (node (ref "U1") (pin "10") (pinfunction "VSS_1_10") (pintype "passive"))
      (node (ref "U1") (pin "19") (pinfunction "VSSA_19") (pintype "passive"))
      (node (ref "U1") (pin "27") (pinfunction "VDD_2_27") (pintype "passive"))
      (node (ref "U1") (pin "49") (pinfunction "VSS_3_49") (pintype "passive"))
      (node (ref "U1") (pin "74") (pinfunction "VSS_4_74") (pintype "passive"))
      (node (ref "U1") (pin "99") (pinfunction "VSS_5_99") (pintype "passive"))
      (node (ref "Y1") (pin "2") (pinfunction "GND_1_2") (pintype "passive"))
      (node (ref "Y1") (pin "4") (pinfunction "GND_2_4") (pintype "passive"))
    )
    (net (code "70") (name "Net-(DS1-A)") (class "Default")
      (node (ref "DS1") (pin "1") (pinfunction "A_1") (pintype "passive"))
      (node (ref "R18") (pin "2") (pinfunction "2_2") (pintype "passive"))
    )
    (net (code "71") (name "Net-(DS2-A)") (class "Default")
      (node (ref "DS2") (pin "1") (pinfunction "A_1") (pintype "passive"))
      (node (ref "R19") (pin "2") (pinfunction "2_2") (pintype "passive"))
    )
    (net (code "72") (name "Net-(DS3-A)") (class "Default")
      (node (ref "DS3") (pin "1") (pinfunction "A_1") (pintype "passive"))
      (node (ref "R20") (pin "2") (pinfunction "2_2") (pintype "passive"))
    )
    (net (code "73") (name "VBAT") (class "Default")
      (node (ref "D2") (pin "C") (pinfunction "C_C") (pintype "passive"))
      (node (ref "J4") (pin "1") (pinfunction "1_1") (pintype "passive"))
      (node (ref "R13") (pin "1") (pinfunction "1_1") (pintype "passive"))
      (node (ref "R19") (pin "1") (pinfunction "1_1") (pintype "passive"))
    )
    (net (code "74") (name "VBUS") (class "Default")
      (node (ref "IC2") (pin "5") (pinfunction "VBUS_5") (pintype "passive"))
      (node (ref "J1") (pin "A4_B9") (pinfunction "VBUS_A_A4_B9") (pintype "power_in"))
      (node (ref "J1") (pin "B4_A9") (pinfunction "VBUS_B_B4_A9") (pintype "power_in"))
      (node (ref "R12") (pin "1") (pinfunction "1_1") (pintype "passive"))
      (node (ref "R18") (pin "1") (pinfunction "1_1") (pintype "passive"))
    )
    (net (code "75") (name "unconnected-(IC1-NC_1-Pad5)") (class "Default")
      (node (ref "IC1") (pin "5") (pinfunction "NC_1_5") (pintype "passive+no_connect"))
    )
    (net (code "76") (name "unconnected-(IC1-NC_2-Pad8)") (class "Default")
      (node (ref "IC1") (pin "8") (pinfunction "NC_2_8") (pintype "passive+no_connect"))
    )
    (net (code "77") (name "unconnected-(J1-SBU1-PadA8)") (class "Default")
      (node (ref "J1") (pin "A8") (pinfunction "SBU1_A8") (pintype "bidirectional+no_connect"))
    )
    (net (code "78") (name "unconnected-(J1-SBU2-PadB8)") (class "Default")
      (node (ref "J1") (pin "B8") (pinfunction "SBU2_B8") (pintype "bidirectional+no_connect"))
    )
    (net (code "79") (name "unconnected-(J4-MNT_1-Pad5)") (class "Default")
      (node (ref "J4") (pin "5") (pinfunction "MNT_1_5") (pintype "passive+no_connect"))
    )
    (net (code "80") (name "unconnected-(J4-MNT_2-Pad6)") (class "Default")
      (node (ref "J4") (pin "6") (pinfunction "MNT_2_6") (pintype "passive+no_connect"))
    )
    (net (code "81") (name "unconnected-(J7-Pad7)") (class "Default")
      (node (ref "J7") (pin "7") (pinfunction "7_7") (pintype "passive+no_connect"))
    )
    (net (code "82") (name "unconnected-(J7-Pad8)") (class "Default")
      (node (ref "J7") (pin "8") (pinfunction "8_8") (pintype "passive+no_connect"))
    )
    (net (code "83") (name "unconnected-(J7-Pad9)") (class "Default")
      (node (ref "J7") (pin "9") (pinfunction "9_9") (pintype "passive+no_connect"))
    )
    (net (code "84") (name "unconnected-(U1-PA0-Pad22)") (class "Default")
      (node (ref "U1") (pin "22") (pinfunction "PA0_22") (pintype "passive+no_connect"))
    )
    (net (code "85") (name "unconnected-(U1-PA1-Pad23)") (class "Default")
      (node (ref "U1") (pin "23") (pinfunction "PA1_23") (pintype "passive+no_connect"))
    )
    (net (code "86") (name "unconnected-(U1-PB0-Pad34)") (class "Default")
      (node (ref "U1") (pin "34") (pinfunction "PB0_34") (pintype "passive+no_connect"))
    )
    (net (code "87") (name "unconnected-(U1-PB1-Pad35)") (class "Default")
      (node (ref "U1") (pin "35") (pinfunction "PB1_35") (pintype "passive+no_connect"))
    )
    (net (code "88") (name "unconnected-(U1-PB2-Pad36)") (class "Default")
      (node (ref "U1") (pin "36") (pinfunction "PB2_36") (pintype "passive+no_connect"))
    )
    (net (code "89") (name "unconnected-(U1-PB4-Pad90)") (class "Default")
      (node (ref "U1") (pin "90") (pinfunction "PB4_90") (pintype "passive+no_connect"))
    )
    (net (code "90") (name "unconnected-(U1-PB5-Pad91)") (class "Default")
      (node (ref "U1") (pin "91") (pinfunction "PB5_91") (pintype "passive+no_connect"))
    )
    (net (code "91") (name "unconnected-(U1-PB14-Pad53)") (class "Default")
      (node (ref "U1") (pin "53") (pinfunction "PB14_53") (pintype "passive+no_connect"))
    )
    (net (code "92") (name "unconnected-(U1-PB15-Pad54)") (class "Default")
      (node (ref "U1") (pin "54") (pinfunction "PB15_54") (pintype "passive+no_connect"))
    )
    (net (code "93") (name "unconnected-(U1-PC0-Pad15)") (class "Default")
      (node (ref "U1") (pin "15") (pinfunction "PC0_15") (pintype "passive+no_connect"))
    )
    (net (code "94") (name "unconnected-(U1-PC3_C-Pad18)") (class "Default")
      (node (ref "U1") (pin "18") (pinfunction "PC3_C_18") (pintype "passive+no_connect"))
    )
    (net (code "95") (name "unconnected-(U1-PC5-Pad33)") (class "Default")
      (node (ref "U1") (pin "33") (pinfunction "PC5_33") (pintype "passive+no_connect"))
    )
    (net (code "96") (name "unconnected-(U1-PC8-Pad65)") (class "Default")
      (node (ref "U1") (pin "65") (pinfunction "PC8_65") (pintype "passive+no_connect"))
    )
    (net (code "97") (name "unconnected-(U1-PC13-SD_PWR_EN-Pad7)") (class "Default")
      (node (ref "U1") (pin "7") (pinfunction "PC13-SD_PWR_EN_7") (pintype "passive+no_connect"))
    )
    (net (code "98") (name "unconnected-(U1-PC14-OSC32_IN-Pad8)") (class "Default")
      (node (ref "U1") (pin "8") (pinfunction "PC14-OSC32_IN_8") (pintype "passive+no_connect"))
    )
    (net (code "99") (name "unconnected-(U1-PC15-OSC32_OUT-Pad9)") (class "Default")
      (node (ref "U1") (pin "9") (pinfunction "PC15-OSC32_OUT_9") (pintype "passive+no_connect"))
    )
    (net (code "100") (name "unconnected-(U1-PD1-Pad82)") (class "Default")
      (node (ref "U1") (pin "82") (pinfunction "PD1_82") (pintype "passive+no_connect"))
    )
    (net (code "101") (name "unconnected-(U1-PD2-Pad83)") (class "Default")
      (node (ref "U1") (pin "83") (pinfunction "PD2_83") (pintype "passive+no_connect"))
    )
    (net (code "102") (name "unconnected-(U1-PD3-Pad84)") (class "Default")
      (node (ref "U1") (pin "84") (pinfunction "PD3_84") (pintype "passive+no_connect"))
    )
    (net (code "103") (name "unconnected-(U1-PD4-Pad85)") (class "Default")
      (node (ref "U1") (pin "85") (pinfunction "PD4_85") (pintype "passive+no_connect"))
    )
    (net (code "104") (name "unconnected-(U1-PD7-Pad88)") (class "Default")
      (node (ref "U1") (pin "88") (pinfunction "PD7_88") (pintype "passive+no_connect"))
    )
    (net (code "105") (name "unconnected-(U1-PD10-Pad57)") (class "Default")
      (node (ref "U1") (pin "57") (pinfunction "PD10_57") (pintype "passive+no_connect"))
    )
    (net (code "106") (name "unconnected-(U1-PD11-Pad58)") (class "Default")
      (node (ref "U1") (pin "58") (pinfunction "PD11_58") (pintype "passive+no_connect"))
    )
    (net (code "107") (name "unconnected-(U1-PD12-Pad59)") (class "Default")
      (node (ref "U1") (pin "59") (pinfunction "PD12_59") (pintype "passive+no_connect"))
    )
    (net (code "108") (name "unconnected-(U1-PD13-Pad60)") (class "Default")
      (node (ref "U1") (pin "60") (pinfunction "PD13_60") (pintype "passive+no_connect"))
    )
    (net (code "109") (name "unconnected-(U1-PD14-Pad61)") (class "Default")
      (node (ref "U1") (pin "61") (pinfunction "PD14_61") (pintype "passive+no_connect"))
    )
    (net (code "110") (name "unconnected-(U1-PD15-Pad62)") (class "Default")
      (node (ref "U1") (pin "62") (pinfunction "PD15_62") (pintype "passive+no_connect"))
    )
    (net (code "111") (name "unconnected-(U1-PE0-UART8_RX-Pad97)") (class "Default")
      (node (ref "U1") (pin "97") (pinfunction "PE0-UART8_RX_97") (pintype "passive+no_connect"))
    )
    (net (code "112") (name "unconnected-(U1-PE1-UART8_TX-Pad98)") (class "Default")
      (node (ref "U1") (pin "98") (pinfunction "PE1-UART8_TX_98") (pintype "passive+no_connect"))
    )
    (net (code "113") (name "unconnected-(U1-PE10-Pad40)") (class "Default")
      (node (ref "U1") (pin "40") (pinfunction "PE10_40") (pintype "passive+no_connect"))
    )
    (net (code "114") (name "unconnected-(U1-PE12-Pad42)") (class "Default")
      (node (ref "U1") (pin "42") (pinfunction "PE12_42") (pintype "passive+no_connect"))
    )
    (net (code "115") (name "unconnected-(U1-PE15-Pad45)") (class "Default")
      (node (ref "U1") (pin "45") (pinfunction "PE15_45") (pintype "passive+no_connect"))
    )
  )
)
